# SCH_sonnn_2025-09-09_1.net
KiCad netlist of a schematic drawn in EasyEDA
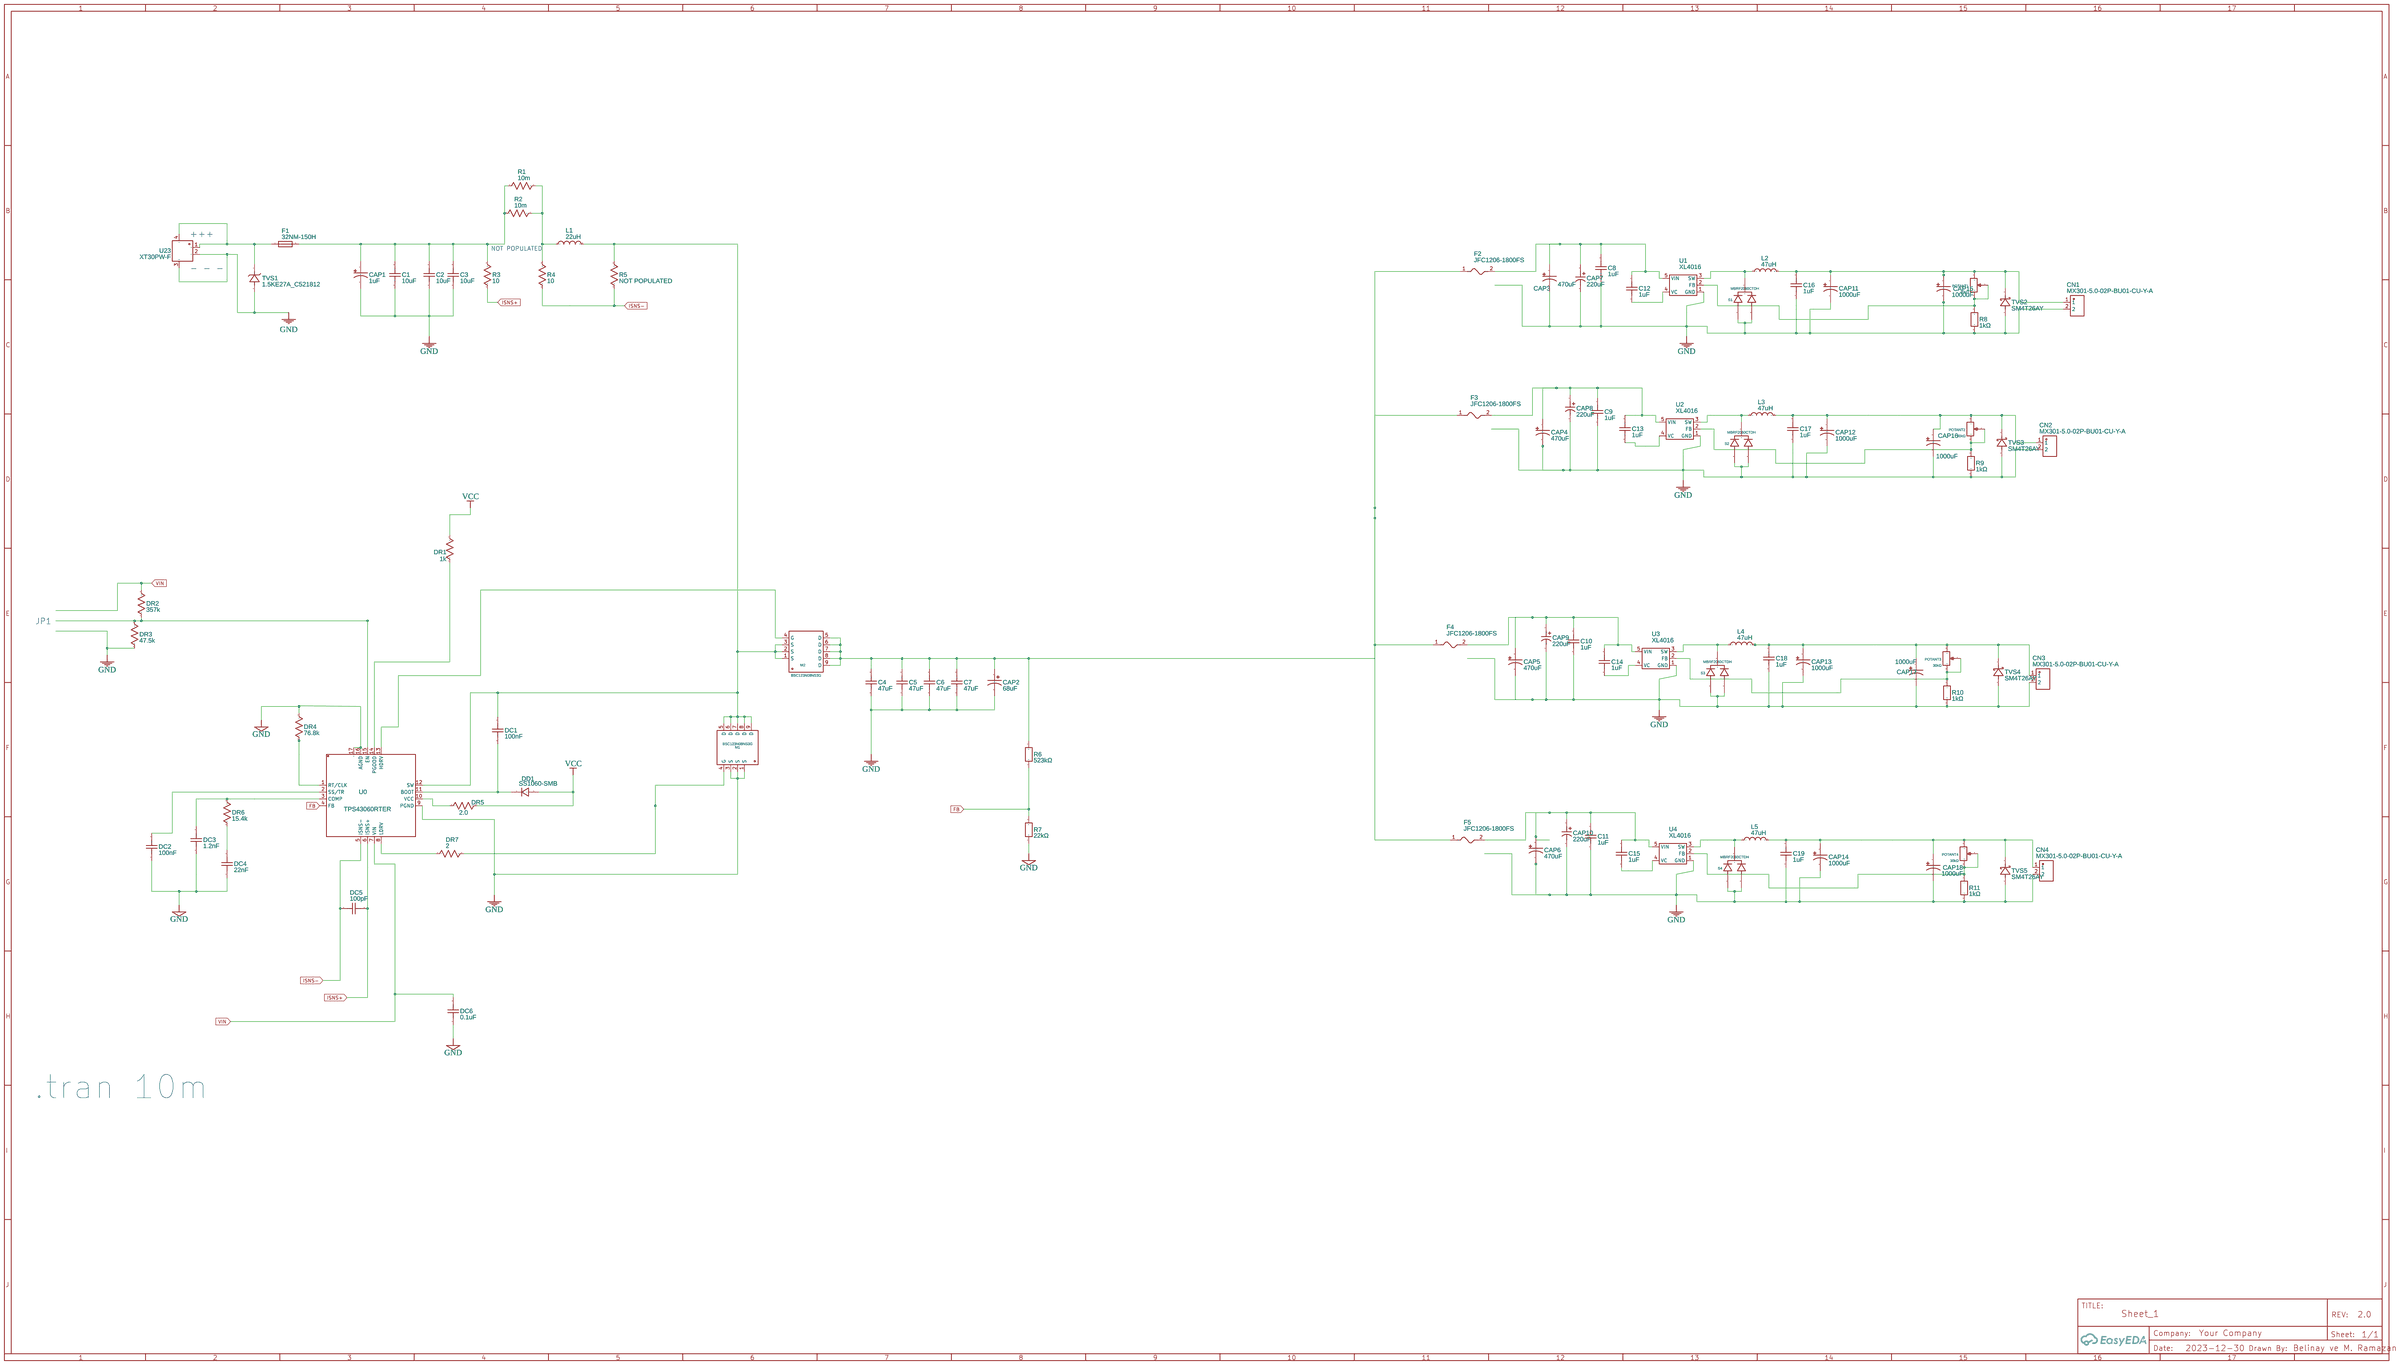
[diagram p0: schematic sheet]

(export (version "E")
  (design (tool "Eeschema 10.0.6"))
  (components
    (comp (ref "C1")
      (value "10uF")
      (fields (field (name "Manufacturer Part") "CNC6P1X7R1H106K250AE") (field (name "Manufacturer") "TDK"))
      (libsource (lib "") (part "CNC6P1X7R1H106K250AE"))
    )
    (comp (ref "C2")
      (value "10uF")
      (fields (field (name "Manufacturer Part") "CNC6P1X7R1H106K250AE") (field (name "Manufacturer") "TDK"))
      (libsource (lib "") (part "CNC6P1X7R1H106K250AE"))
    )
    (comp (ref "C3")
      (value "10uF")
      (fields (field (name "Manufacturer Part") "CNC6P1X7R1H106K250AE") (field (name "Manufacturer") "TDK"))
      (libsource (lib "") (part "CNC6P1X7R1H106K250AE"))
    )
    (comp (ref "C4") (value "47uF") (libsource (lib "") (part "C_0603_US")))
    (comp (ref "C5") (value "47uF") (libsource (lib "") (part "C_0603_US")))
    (comp (ref "C6") (value "47uF") (libsource (lib "") (part "C_0603_US")))
    (comp (ref "C7") (value "47uF") (libsource (lib "") (part "C_0603_US")))
    (comp (ref "C8")
      (value "1uF")
      (fields (field (name "Manufacturer Part") "FK26X7R1H105KRE06") (field (name "Manufacturer") "TDK"))
      (libsource (lib "") (part "FK26X7R1H105KRE06"))
    )
    (comp (ref "C9")
      (value "1uF")
      (fields (field (name "Manufacturer Part") "FK26X7R1H105KRE06") (field (name "Manufacturer") "TDK"))
      (libsource (lib "") (part "FK26X7R1H105KRE06"))
    )
    (comp (ref "C10")
      (value "1uF")
      (fields (field (name "Manufacturer Part") "FK26X7R1H105KRE06") (field (name "Manufacturer") "TDK"))
      (libsource (lib "") (part "FK26X7R1H105KRE06"))
    )
    (comp (ref "C11")
      (value "1uF")
      (fields (field (name "Manufacturer Part") "FK26X7R1H105KRE06") (field (name "Manufacturer") "TDK"))
      (libsource (lib "") (part "FK26X7R1H105KRE06"))
    )
    (comp (ref "C12")
      (value "1uF")
      (fields (field (name "Manufacturer Part") "C1005X6S1A105K050BC") (field (name "Manufacturer") "TDK"))
      (libsource (lib "") (part "C1005X6S1A105K050BC"))
    )
    (comp (ref "C13")
      (value "1uF")
      (fields (field (name "Manufacturer Part") "C1005X6S1A105K050BC") (field (name "Manufacturer") "TDK"))
      (libsource (lib "") (part "C1005X6S1A105K050BC"))
    )
    (comp (ref "C14")
      (value "1uF")
      (fields (field (name "Manufacturer Part") "C1005X6S1A105K050BC") (field (name "Manufacturer") "TDK"))
      (libsource (lib "") (part "C1005X6S1A105K050BC"))
    )
    (comp (ref "C15")
      (value "1uF")
      (fields (field (name "Manufacturer Part") "C1005X6S1A105K050BC") (field (name "Manufacturer") "TDK"))
      (libsource (lib "") (part "C1005X6S1A105K050BC_1"))
    )
    (comp (ref "C16")
      (value "1uF")
      (fields (field (name "Manufacturer Part") "FK26X7R1H105KRE06") (field (name "Manufacturer") "TDK"))
      (libsource (lib "") (part "FK26X7R1H105KRE06"))
    )
    (comp (ref "C17")
      (value "1uF")
      (fields (field (name "Manufacturer Part") "FK26X7R1H105KRE06") (field (name "Manufacturer") "TDK"))
      (libsource (lib "") (part "FK26X7R1H105KRE06_1"))
    )
    (comp (ref "C18")
      (value "1uF")
      (fields (field (name "Manufacturer Part") "FK26X7R1H105KRE06") (field (name "Manufacturer") "TDK"))
      (libsource (lib "") (part "FK26X7R1H105KRE06"))
    )
    (comp (ref "C19")
      (value "1uF")
      (fields (field (name "Manufacturer Part") "FK26X7R1H105KRE06") (field (name "Manufacturer") "TDK"))
      (libsource (lib "") (part "FK26X7R1H105KRE06"))
    )
    (comp (ref "CAP1")
      (value "1uF")
      (fields (field (name "Manufacturer Part") "HT2A1R0M0405") (field (name "Manufacturer") "HONOR(荣誉)"))
      (libsource (lib "") (part "RVT2A1R0M0405"))
    )
    (comp (ref "CAP2") (value "68uF") (libsource (lib "") (part "C_Tan_SMD_A_US")))
    (comp (ref "CAP3")
      (value "470uF")
      (fields
        (field (name "Manufacturer Part") "RC063M471LO13*20TH-2A1E")
        (field (name "Manufacturer") "BERYL(绿宝石)")
      )
      (libsource (lib "") (part "RC063M471LO13*20TH-2A1E"))
    )
    (comp (ref "CAP4")
      (value "470uF")
      (fields
        (field (name "Manufacturer Part") "RC063M471LO13*20TH-2A1E")
        (field (name "Manufacturer") "BERYL(绿宝石)")
      )
      (libsource (lib "") (part "RC063M471LO13*20TH-2A1E"))
    )
    (comp (ref "CAP5")
      (value "470uF")
      (fields
        (field (name "Manufacturer Part") "RC063M471LO13*20TH-2A1E")
        (field (name "Manufacturer") "BERYL(绿宝石)")
      )
      (libsource (lib "") (part "RC063M471LO13*20TH-2A1E"))
    )
    (comp (ref "CAP6")
      (value "470uF")
      (fields
        (field (name "Manufacturer Part") "RC063M471LO13*20TH-2A1E")
        (field (name "Manufacturer") "BERYL(绿宝石)")
      )
      (libsource (lib "") (part "RC063M471LO13*20TH-2A1E_1"))
    )
    (comp (ref "CAP7")
      (value "220uF")
      (fields (field (name "Manufacturer Part") "189RV0038") (field (name "Manufacturer") "KNSCHA(科尼盛)"))
      (libsource (lib "") (part "189RV0038"))
    )
    (comp (ref "CAP8")
      (value "220uF")
      (fields (field (name "Manufacturer Part") "189RV0038") (field (name "Manufacturer") "KNSCHA(科尼盛)"))
      (libsource (lib "") (part "189RV0038"))
    )
    (comp (ref "CAP9")
      (value "220uF")
      (fields (field (name "Manufacturer Part") "189RV0038") (field (name "Manufacturer") "KNSCHA(科尼盛)"))
      (libsource (lib "") (part "189RV0038"))
    )
    (comp (ref "CAP10")
      (value "220uF")
      (fields (field (name "Manufacturer Part") "189RV0038") (field (name "Manufacturer") "KNSCHA(科尼盛)"))
      (libsource (lib "") (part "189RV0038"))
    )
    (comp (ref "CAP11")
      (value "1000uF")
      (fields (field (name "Manufacturer Part") "PKCL2001H102MF") (field (name "Manufacturer") "Ymin(永铭)"))
      (libsource (lib "") (part "PKCL21H102MF"))
    )
    (comp (ref "CAP12")
      (value "1000uF")
      (fields (field (name "Manufacturer Part") "PKCL2001H102MF") (field (name "Manufacturer") "Ymin(永铭)"))
      (libsource (lib "") (part "PKCL21H102MF"))
    )
    (comp (ref "CAP13")
      (value "1000uF")
      (fields (field (name "Manufacturer Part") "PKCL2001H102MF") (field (name "Manufacturer") "Ymin(永铭)"))
      (libsource (lib "") (part "PKCL21H102MF"))
    )
    (comp (ref "CAP14")
      (value "1000uF")
      (fields (field (name "Manufacturer Part") "PKCL2001H102MF") (field (name "Manufacturer") "Ymin(永铭)"))
      (libsource (lib "") (part "PKCL21H102MF_1"))
    )
    (comp (ref "CAP15")
      (value "1000uF")
      (fields (field (name "Manufacturer Part") "LKML3001J102MF") (field (name "Manufacturer") "Ymin(永铭)"))
      (libsource (lib "") (part "LKML3001J102MF"))
    )
    (comp (ref "CAP16")
      (value "1000uF")
      (fields (field (name "Manufacturer Part") "LKML3001J102MF") (field (name "Manufacturer") "Ymin(永铭)"))
      (libsource (lib "") (part "LKML3001J102MF"))
    )
    (comp (ref "CAP17")
      (value "1000uF")
      (fields (field (name "Manufacturer Part") "LKML3001J102MF") (field (name "Manufacturer") "Ymin(永铭)"))
      (libsource (lib "") (part "LKML3001J102MF_1"))
    )
    (comp (ref "CAP18")
      (value "1000uF")
      (fields (field (name "Manufacturer Part") "LKML3001J102MF") (field (name "Manufacturer") "Ymin(永铭)"))
      (libsource (lib "") (part "LKML3001J102MF_1"))
    )
    (comp (ref "CN1")
      (value "MX301-5.0-02P-BU01-CU-Y-A")
      (fields
        (field (name "Manufacturer Part") "MX301-5.0-02P-BU01-Cu-Y-A")
        (field (name "Manufacturer") "MAX(迈旭)")
      )
      (libsource (lib "") (part "MX301-5.0-02P-BU01-CU-Y-A"))
    )
    (comp (ref "CN2")
      (value "MX301-5.0-02P-BU01-CU-Y-A")
      (fields
        (field (name "Manufacturer Part") "MX301-5.0-02P-BU01-Cu-Y-A")
        (field (name "Manufacturer") "MAX(迈旭)")
      )
      (libsource (lib "") (part "MX301-5.0-02P-BU01-CU-Y-A"))
    )
    (comp (ref "CN3")
      (value "MX301-5.0-02P-BU01-CU-Y-A")
      (fields
        (field (name "Manufacturer Part") "MX301-5.0-02P-BU01-Cu-Y-A")
        (field (name "Manufacturer") "MAX(迈旭)")
      )
      (libsource (lib "") (part "MX301-5.0-02P-BU01-CU-Y-A"))
    )
    (comp (ref "CN4")
      (value "MX301-5.0-02P-BU01-CU-Y-A")
      (fields
        (field (name "Manufacturer Part") "MX301-5.0-02P-BU01-Cu-Y-A")
        (field (name "Manufacturer") "MAX(迈旭)")
      )
      (libsource (lib "") (part "MX301-5.0-02P-BU01-CU-Y-A"))
    )
    (comp (ref "DC1")
      (value "100nF")
      (fields
        (field (name "Manufacturer Part") "DCS104M26Y5UH6FJ5A0")
        (field (name "Manufacturer") "SHM(南方宏明)")
      )
      (libsource (lib "") (part "DCS104M26Y5UH6FJ5A0"))
    )
    (comp (ref "DC2")
      (value "100nF")
      (fields
        (field (name "Manufacturer Part") "DCS104M26Y5UH6FJ5A0")
        (field (name "Manufacturer") "SHM(南方宏明)")
      )
      (libsource (lib "") (part "DCS104M26Y5UH6FJ5A0_1"))
    )
    (comp (ref "DC3")
      (value "1.2nF")
      (fields (field (name "Manufacturer Part") "PE122J2A0501") (field (name "Manufacturer") "KYET(科雅)"))
      (libsource (lib "") (part "PE122J2A0501"))
    )
    (comp (ref "DC4")
      (value "22nF")
      (fields
        (field (name "Manufacturer Part") "DCM223M39Y5VL6FJ5A0")
        (field (name "Manufacturer") "SHM(南方宏明)")
      )
      (libsource (lib "") (part "DCM223M39Y5VL6FJ5A0"))
    )
    (comp (ref "DC5")
      (value "100pF")
      (fields
        (field (name "Manufacturer Part") "DCC101J26COHF6FJ5A0")
        (field (name "Manufacturer") "SHM(南方宏明)")
      )
      (libsource (lib "") (part "DCC101J26COHF6FJ5A0"))
    )
    (comp (ref "DC6") (value "0.1uF") (libsource (lib "") (part "C_0603_US_1")))
    (comp (ref "DD1")
      (value "SS1060-SMB")
      (fields (field (name "Manufacturer") "GOODWORK(固得沃克)"))
      (libsource (lib "") (part "SS1060-SMB"))
    )
    (comp (ref "DR1") (value "1k") (libsource (lib "") (part "R_AXIAL-0.3_US")))
    (comp (ref "DR2") (value "357k") (libsource (lib "") (part "R_AXIAL-0.3_US")))
    (comp (ref "DR3") (value "47.5k") (libsource (lib "") (part "R_AXIAL-0.3_US")))
    (comp (ref "DR4") (value "76.8k") (libsource (lib "") (part "R_AXIAL-0.3_US")))
    (comp (ref "DR5") (value "2.0") (libsource (lib "") (part "R_AXIAL-0.3_US_3")))
    (comp (ref "DR6") (value "15.4k") (libsource (lib "") (part "R_AXIAL-0.3_US")))
    (comp (ref "DR7") (value "2") (libsource (lib "") (part "R_0603_US")))
    (comp (ref "F1")
      (value "32NM-150H")
      (fields (field (name "Manufacturer") "HOLLY(好利来)"))
      (libsource (lib "") (part "32NM-150H"))
    )
    (comp (ref "F2")
      (value "JFC1206-1800FS")
      (fields (field (name "Manufacturer") "JDTfuse(集电通)"))
      (libsource (lib "") (part "JFC1206-1800FS"))
    )
    (comp (ref "F3")
      (value "JFC1206-1800FS")
      (fields (field (name "Manufacturer") "JDTfuse(集电通)"))
      (libsource (lib "") (part "JFC1206-1800FS"))
    )
    (comp (ref "F4")
      (value "JFC1206-1800FS")
      (fields (field (name "Manufacturer") "JDTfuse(集电通)"))
      (libsource (lib "") (part "JFC1206-1800FS"))
    )
    (comp (ref "F5")
      (value "JFC1206-1800FS")
      (fields (field (name "Manufacturer") "JDTfuse(集电通)"))
      (libsource (lib "") (part "JFC1206-1800FS"))
    )
    (comp (ref "L1")
      (value "22uH")
      (fields
        (field (name "Manufacturer Part") "PDMTAT068125-220MLU")
        (field (name "Manufacturer") "PROD(谱罗德)")
      )
      (libsource (lib "") (part "PDMTAT068125-220MLU"))
    )
    (comp (ref "L2")
      (value "47uH")
      (fields (field (name "Manufacturer Part") "PDPMAA1712-470MP") (field (name "Manufacturer") "PROD(谱罗德)"))
      (libsource (lib "") (part "PDPMAA1712-470MP"))
    )
    (comp (ref "L3")
      (value "47uH")
      (fields (field (name "Manufacturer Part") "PDPMAA1712-470MP") (field (name "Manufacturer") "PROD(谱罗德)"))
      (libsource (lib "") (part "PDPMAA1712-470MP"))
    )
    (comp (ref "L4")
      (value "47uH")
      (fields (field (name "Manufacturer Part") "PDPMAA1712-470MP") (field (name "Manufacturer") "PROD(谱罗德)"))
      (libsource (lib "") (part "PDPMAA1712-470MP"))
    )
    (comp (ref "L5")
      (value "47uH")
      (fields (field (name "Manufacturer Part") "PDPMAA1712-470MP") (field (name "Manufacturer") "PROD(谱罗德)"))
      (libsource (lib "") (part "PDPMAA1712-470MP"))
    )
    (comp (ref "M1")
      (value "BSC123N08NS3G")
      (fields (field (name "Manufacturer") "Infineon(英飞凌)"))
      (libsource (lib "") (part "BSC123N08NS3G"))
    )
    (comp (ref "M2")
      (value "BSC123N08NS3G")
      (fields (field (name "Manufacturer") "Infineon(英飞凌)"))
      (libsource (lib "") (part "BSC123N08NS3G_1"))
    )
    (comp (ref "POTANT1")
      (value "30kΩ")
      (fields (field (name "Manufacturer Part") "3362P-1-103LF") (field (name "Manufacturer") "BOURNS"))
      (libsource (lib "") (part "3362P-1-103LF"))
    )
    (comp (ref "POTANT2")
      (value "30kΩ")
      (fields (field (name "Manufacturer Part") "3362P-1-103LF") (field (name "Manufacturer") "BOURNS"))
      (libsource (lib "") (part "3362P-1-103LF"))
    )
    (comp (ref "POTANT3")
      (value "30kΩ")
      (fields (field (name "Manufacturer Part") "3362P-1-103LF") (field (name "Manufacturer") "BOURNS"))
      (libsource (lib "") (part "3362P-1-103LF"))
    )
    (comp (ref "POTANT4")
      (value "30kΩ")
      (fields (field (name "Manufacturer Part") "3362P-1-103LF") (field (name "Manufacturer") "BOURNS"))
      (libsource (lib "") (part "3362P-1-103LF"))
    )
    (comp (ref "R1") (value "10m") (libsource (lib "") (part "R_AXIAL-0.3_US_2")))
    (comp (ref "R2") (value "10m") (libsource (lib "") (part "R_AXIAL-0.3_US_2")))
    (comp (ref "R3") (value "10") (libsource (lib "") (part "R_AXIAL-0.3_US_1")))
    (comp (ref "R4") (value "10") (libsource (lib "") (part "R_AXIAL-0.3_US_1")))
    (comp (ref "R5") (value "NOT POPULATED") (libsource (lib "") (part "R_AXIAL-0.3_US_1")))
    (comp (ref "R6")
      (value "523kΩ")
      (fields (field (name "Manufacturer Part") "MFR-25FBF52-523K") (field (name "Manufacturer") "YAGEO(国巨)"))
      (libsource (lib "") (part "MFR-25FBF52-523K"))
    )
    (comp (ref "R7")
      (value "22kΩ")
      (fields
        (field (name "Manufacturer Part") "RN 3WS 22K F T/B A1")
        (field (name "Manufacturer") "Tyohm(幸亚电阻)")
      )
      (libsource (lib "") (part "RN 3WS 22K F T/B A1"))
    )
    (comp (ref "R8")
      (value "1kΩ")
      (fields (field (name "Manufacturer Part") "MF0207FTE52-1K") (field (name "Manufacturer") "YAGEO(国巨)"))
      (libsource (lib "") (part "MF0207FTE52-1K"))
    )
    (comp (ref "R9")
      (value "1kΩ")
      (fields (field (name "Manufacturer Part") "MF0207FTE52-1K") (field (name "Manufacturer") "YAGEO(国巨)"))
      (libsource (lib "") (part "MF0207FTE52-1K"))
    )
    (comp (ref "R10")
      (value "1kΩ")
      (fields (field (name "Manufacturer Part") "MF0207FTE52-1K") (field (name "Manufacturer") "YAGEO(国巨)"))
      (libsource (lib "") (part "MF0207FTE52-1K"))
    )
    (comp (ref "R11")
      (value "1kΩ")
      (fields (field (name "Manufacturer Part") "MF0207FTE52-1K") (field (name "Manufacturer") "YAGEO(国巨)"))
      (libsource (lib "") (part "MF0207FTE52-1K"))
    )
    (comp (ref "S1")
      (value "MBRF2060CTDH")
      (fields (field (name "Manufacturer") "迪一"))
      (libsource (lib "") (part "MBRF2060CTDH"))
    )
    (comp (ref "S2")
      (value "MBRF2060CTDH")
      (fields (field (name "Manufacturer") "迪一"))
      (libsource (lib "") (part "MBRF2060CTDH"))
    )
    (comp (ref "S3")
      (value "MBRF2060CTDH")
      (fields (field (name "Manufacturer") "迪一"))
      (libsource (lib "") (part "MBRF2060CTDH"))
    )
    (comp (ref "S4")
      (value "MBRF2060CTDH")
      (fields (field (name "Manufacturer") "迪一"))
      (libsource (lib "") (part "MBRF2060CTDH"))
    )
    (comp (ref "TVS1")
      (value "1.5KE27A_C521812")
      (fields
        (field (name "Manufacturer Part") "1.5KE27A/B")
        (field (name "Manufacturer") "Brightking(君耀电子)")
      )
      (libsource (lib "") (part "1.5KE27A_C521812"))
    )
    (comp (ref "TVS2")
      (value "SM4T26AY")
      (fields (field (name "Manufacturer") "ST(意法半导体)"))
      (libsource (lib "") (part "SM4T26AY"))
    )
    (comp (ref "TVS3")
      (value "SM4T26AY")
      (fields (field (name "Manufacturer") "ST(意法半导体)"))
      (libsource (lib "") (part "SM4T26AY"))
    )
    (comp (ref "TVS4")
      (value "SM4T26AY")
      (fields (field (name "Manufacturer") "ST(意法半导体)"))
      (libsource (lib "") (part "SM4T26AY"))
    )
    (comp (ref "TVS5")
      (value "SM4T26AY")
      (fields (field (name "Manufacturer") "ST(意法半导体)"))
      (libsource (lib "") (part "SM4T26AY"))
    )
    (comp (ref "U0")
      (value "TPS43060RTER")
      (fields (field (name "Manufacturer") "TI(德州仪器)"))
      (libsource (lib "") (part "TPS43060RTER"))
    )
    (comp (ref "U1")
      (value "XL4016")
      (fields (field (name "Manufacturer Part") "XL4016E1") (field (name "Manufacturer") "XLSEMI"))
      (libsource (lib "") (part "XL4016"))
    )
    (comp (ref "U2")
      (value "XL4016")
      (fields (field (name "Manufacturer Part") "XL4016E1") (field (name "Manufacturer") "XLSEMI"))
      (libsource (lib "") (part "XL4016"))
    )
    (comp (ref "U3")
      (value "XL4016")
      (fields (field (name "Manufacturer Part") "XL4016E1") (field (name "Manufacturer") "XLSEMI"))
      (libsource (lib "") (part "XL4016"))
    )
    (comp (ref "U4")
      (value "XL4016")
      (fields (field (name "Manufacturer Part") "XL4016E1") (field (name "Manufacturer") "XLSEMI"))
      (libsource (lib "") (part "XL4016"))
    )
    (comp (ref "U23") (value "XT30PW-F") (libsource (lib "") (part "XT30PW-F")))
  )
  (nets
    (net (code "1") (name "FB") (class "Default")
      (node (ref "R6") (pin "1") (pinfunction "1_1") (pintype "unspecified"))
      (node (ref "R7") (pin "1") (pinfunction "1_1") (pintype "unspecified"))
      (node (ref "U0") (pin "4") (pinfunction "FB_4") (pintype "unspecified"))
    )
    (net (code "2") (name "GND") (class "Default")
      (node (ref "C1") (pin "1") (pinfunction "1_1") (pintype "unspecified"))
      (node (ref "C10") (pin "2") (pinfunction "2_2") (pintype "unspecified"))
      (node (ref "C11") (pin "2") (pinfunction "2_2") (pintype "unspecified"))
      (node (ref "C16") (pin "2") (pinfunction "2_2") (pintype "unspecified"))
      (node (ref "C17") (pin "1") (pinfunction "1_1") (pintype "unspecified"))
      (node (ref "C18") (pin "2") (pinfunction "2_2") (pintype "unspecified"))
      (node (ref "C19") (pin "2") (pinfunction "2_2") (pintype "unspecified"))
      (node (ref "C2") (pin "1") (pinfunction "1_1") (pintype "unspecified"))
      (node (ref "C3") (pin "1") (pinfunction "1_1") (pintype "unspecified"))
      (node (ref "C4") (pin "1") (pinfunction "1_1") (pintype "unspecified"))
      (node (ref "C5") (pin "1") (pinfunction "1_1") (pintype "unspecified"))
      (node (ref "C6") (pin "1") (pinfunction "1_1") (pintype "unspecified"))
      (node (ref "C7") (pin "1") (pinfunction "1_1") (pintype "unspecified"))
      (node (ref "C8") (pin "2") (pinfunction "2_2") (pintype "unspecified"))
      (node (ref "C9") (pin "2") (pinfunction "2_2") (pintype "unspecified"))
      (node (ref "CAP1") (pin "2") (pinfunction "2_2") (pintype "unspecified"))
      (node (ref "CAP10") (pin "2") (pinfunction "2_2") (pintype "input"))
      (node (ref "CAP11") (pin "2") (pinfunction "2_2") (pintype "unspecified"))
      (node (ref "CAP12") (pin "2") (pinfunction "2_2") (pintype "unspecified"))
      (node (ref "CAP13") (pin "2") (pinfunction "2_2") (pintype "unspecified"))
      (node (ref "CAP14") (pin "2") (pinfunction "2_2") (pintype "unspecified"))
      (node (ref "CAP15") (pin "2") (pinfunction "2_2") (pintype "unspecified"))
      (node (ref "CAP16") (pin "2") (pinfunction "2_2") (pintype "unspecified"))
      (node (ref "CAP17") (pin "2") (pinfunction "2_2") (pintype "unspecified"))
      (node (ref "CAP18") (pin "2") (pinfunction "2_2") (pintype "unspecified"))
      (node (ref "CAP2") (pin "2") (pinfunction "2_2") (pintype "unspecified"))
      (node (ref "CAP3") (pin "2") (pinfunction "2_2") (pintype "unspecified"))
      (node (ref "CAP4") (pin "2") (pinfunction "2_2") (pintype "unspecified"))
      (node (ref "CAP5") (pin "2") (pinfunction "2_2") (pintype "unspecified"))
      (node (ref "CAP6") (pin "2") (pinfunction "2_2") (pintype "unspecified"))
      (node (ref "CAP7") (pin "2") (pinfunction "2_2") (pintype "input"))
      (node (ref "CAP8") (pin "2") (pinfunction "2_2") (pintype "input"))
      (node (ref "CAP9") (pin "2") (pinfunction "2_2") (pintype "input"))
      (node (ref "CN1") (pin "2") (pinfunction "2_2") (pintype "unspecified"))
      (node (ref "CN2") (pin "2") (pinfunction "2_2") (pintype "unspecified"))
      (node (ref "CN3") (pin "2") (pinfunction "2_2") (pintype "unspecified"))
      (node (ref "CN4") (pin "2") (pinfunction "2_2") (pintype "unspecified"))
      (node (ref "DC2") (pin "1") (pinfunction "1_1") (pintype "unspecified"))
      (node (ref "DC3") (pin "1") (pinfunction "1_1") (pintype "unspecified"))
      (node (ref "DC4") (pin "1") (pinfunction "1_1") (pintype "unspecified"))
      (node (ref "DC6") (pin "1") (pinfunction "1_1") (pintype "unspecified"))
      (node (ref "DR3") (pin "1") (pinfunction "1_1") (pintype "unspecified"))
      (node (ref "DR4") (pin "2") (pinfunction "2_2") (pintype "unspecified"))
      (node (ref "M1") (pin "1") (pinfunction "S_1") (pintype "unspecified"))
      (node (ref "M1") (pin "2") (pinfunction "S_2") (pintype "unspecified"))
      (node (ref "M1") (pin "3") (pinfunction "S_3") (pintype "unspecified"))
      (node (ref "R10") (pin "2") (pinfunction "2_2") (pintype "unspecified"))
      (node (ref "R11") (pin "2") (pinfunction "2_2") (pintype "unspecified"))
      (node (ref "R7") (pin "2") (pinfunction "2_2") (pintype "unspecified"))
      (node (ref "R8") (pin "2") (pinfunction "2_2") (pintype "unspecified"))
      (node (ref "R9") (pin "2") (pinfunction "2_2") (pintype "unspecified"))
      (node (ref "S1") (pin "1") (pinfunction "1_1") (pintype "unspecified"))
      (node (ref "S1") (pin "3") (pinfunction "3_3") (pintype "unspecified"))
      (node (ref "S2") (pin "1") (pinfunction "1_1") (pintype "unspecified"))
      (node (ref "S2") (pin "3") (pinfunction "3_3") (pintype "unspecified"))
      (node (ref "S3") (pin "1") (pinfunction "1_1") (pintype "unspecified"))
      (node (ref "S3") (pin "3") (pinfunction "3_3") (pintype "unspecified"))
      (node (ref "S4") (pin "1") (pinfunction "1_1") (pintype "unspecified"))
      (node (ref "S4") (pin "3") (pinfunction "3_3") (pintype "unspecified"))
      (node (ref "TVS1") (pin "2") (pinfunction "A_2") (pintype "unspecified"))
      (node (ref "TVS2") (pin "2") (pinfunction "2_2") (pintype "unspecified"))
      (node (ref "TVS3") (pin "2") (pinfunction "2_2") (pintype "unspecified"))
      (node (ref "TVS4") (pin "2") (pinfunction "2_2") (pintype "unspecified"))
      (node (ref "TVS5") (pin "2") (pinfunction "2_2") (pintype "unspecified"))
      (node (ref "U0") (pin "16") (pinfunction "AGND_16") (pintype "unspecified"))
      (node (ref "U0") (pin "17") (pinfunction "PAD_17") (pintype "unspecified"))
      (node (ref "U0") (pin "9") (pinfunction "PGND_9") (pintype "unspecified"))
      (node (ref "U1") (pin "1") (pinfunction "GND_1") (pintype "unspecified"))
      (node (ref "U2") (pin "1") (pinfunction "GND_1") (pintype "unspecified"))
      (node (ref "U23") (pin "2") (pinfunction "2_2") (pintype "unspecified"))
      (node (ref "U23") (pin "3") (pinfunction "3_3") (pintype "unspecified"))
      (node (ref "U3") (pin "1") (pinfunction "GND_1") (pintype "unspecified"))
      (node (ref "U4") (pin "1") (pinfunction "GND_1") (pintype "unspecified"))
    )
    (net (code "3") (name "ISNS+") (class "Default")
      (node (ref "DC5") (pin "2") (pinfunction "2_2") (pintype "unspecified"))
      (node (ref "R3") (pin "1") (pinfunction "1_1") (pintype "unspecified"))
      (node (ref "U0") (pin "6") (pinfunction "ISNS+_6") (pintype "unspecified"))
    )
    (net (code "4") (name "ISNS-") (class "Default")
      (node (ref "DC5") (pin "1") (pinfunction "1_1") (pintype "unspecified"))
      (node (ref "R4") (pin "1") (pinfunction "1_1") (pintype "unspecified"))
      (node (ref "R5") (pin "1") (pinfunction "1_1") (pintype "unspecified"))
      (node (ref "U0") (pin "5") (pinfunction "ISNS-_5") (pintype "unspecified"))
    )
    (net (code "5") (name "Net-(C1-Pad2)") (class "Default")
      (node (ref "C1") (pin "2") (pinfunction "2_2") (pintype "unspecified"))
      (node (ref "C2") (pin "2") (pinfunction "2_2") (pintype "unspecified"))
      (node (ref "C3") (pin "2") (pinfunction "2_2") (pintype "unspecified"))
      (node (ref "CAP1") (pin "1") (pinfunction "1_1") (pintype "unspecified"))
      (node (ref "F1") (pin "2") (pinfunction "2_2") (pintype "unspecified"))
      (node (ref "R1") (pin "1") (pinfunction "1_1") (pintype "unspecified"))
      (node (ref "R2") (pin "1") (pinfunction "1_1") (pintype "unspecified"))
      (node (ref "R3") (pin "2") (pinfunction "2_2") (pintype "unspecified"))
    )
    (net (code "6") (name "Net-(C4-Pad2)") (class "Default")
      (node (ref "C4") (pin "2") (pinfunction "2_2") (pintype "unspecified"))
      (node (ref "C5") (pin "2") (pinfunction "2_2") (pintype "unspecified"))
      (node (ref "C6") (pin "2") (pinfunction "2_2") (pintype "unspecified"))
      (node (ref "C7") (pin "2") (pinfunction "2_2") (pintype "unspecified"))
      (node (ref "CAP2") (pin "1") (pinfunction "1_1") (pintype "unspecified"))
      (node (ref "F2") (pin "1") (pinfunction "1_1") (pintype "unspecified"))
      (node (ref "F3") (pin "1") (pinfunction "1_1") (pintype "unspecified"))
      (node (ref "F4") (pin "1") (pinfunction "1_1") (pintype "unspecified"))
      (node (ref "F5") (pin "1") (pinfunction "1_1") (pintype "unspecified"))
      (node (ref "M2") (pin "5") (pinfunction "D_5") (pintype "unspecified"))
      (node (ref "M2") (pin "6") (pinfunction "D_6") (pintype "unspecified"))
      (node (ref "M2") (pin "7") (pinfunction "D_7") (pintype "unspecified"))
      (node (ref "M2") (pin "8") (pinfunction "D_8") (pintype "unspecified"))
      (node (ref "M2") (pin "9") (pinfunction "D_9") (pintype "unspecified"))
      (node (ref "R6") (pin "2") (pinfunction "2_2") (pintype "unspecified"))
    )
    (net (code "7") (name "Net-(C16-Pad1)") (class "Default")
      (node (ref "C16") (pin "1") (pinfunction "1_1") (pintype "unspecified"))
      (node (ref "CAP11") (pin "1") (pinfunction "1_1") (pintype "unspecified"))
      (node (ref "CAP15") (pin "1") (pinfunction "1_1") (pintype "unspecified"))
      (node (ref "CN1") (pin "1") (pinfunction "1_1") (pintype "unspecified"))
      (node (ref "L2") (pin "2") (pinfunction "2_2") (pintype "unspecified"))
      (node (ref "POTANT1") (pin "1") (pinfunction "1_1") (pintype "input"))
      (node (ref "TVS2") (pin "1") (pinfunction "1_1") (pintype "unspecified"))
    )
    (net (code "8") (name "Net-(C17-Pad2)") (class "Default")
      (node (ref "C17") (pin "2") (pinfunction "2_2") (pintype "unspecified"))
      (node (ref "CAP12") (pin "1") (pinfunction "1_1") (pintype "unspecified"))
      (node (ref "CAP16") (pin "1") (pinfunction "1_1") (pintype "unspecified"))
      (node (ref "CN2") (pin "1") (pinfunction "1_1") (pintype "unspecified"))
      (node (ref "L3") (pin "2") (pinfunction "2_2") (pintype "unspecified"))
      (node (ref "POTANT2") (pin "1") (pinfunction "1_1") (pintype "input"))
      (node (ref "TVS3") (pin "1") (pinfunction "1_1") (pintype "unspecified"))
    )
    (net (code "9") (name "Net-(C18-Pad1)") (class "Default")
      (node (ref "C18") (pin "1") (pinfunction "1_1") (pintype "unspecified"))
      (node (ref "CAP13") (pin "1") (pinfunction "1_1") (pintype "unspecified"))
      (node (ref "CAP17") (pin "1") (pinfunction "1_1") (pintype "unspecified"))
      (node (ref "CN3") (pin "1") (pinfunction "1_1") (pintype "unspecified"))
      (node (ref "L4") (pin "2") (pinfunction "2_2") (pintype "unspecified"))
      (node (ref "POTANT3") (pin "1") (pinfunction "1_1") (pintype "input"))
      (node (ref "TVS4") (pin "1") (pinfunction "1_1") (pintype "unspecified"))
    )
    (net (code "10") (name "Net-(C19-Pad1)") (class "Default")
      (node (ref "C19") (pin "1") (pinfunction "1_1") (pintype "unspecified"))
      (node (ref "CAP14") (pin "1") (pinfunction "1_1") (pintype "unspecified"))
      (node (ref "CAP18") (pin "1") (pinfunction "1_1") (pintype "unspecified"))
      (node (ref "CN4") (pin "1") (pinfunction "1_1") (pintype "unspecified"))
      (node (ref "L5") (pin "2") (pinfunction "2_2") (pintype "unspecified"))
      (node (ref "POTANT4") (pin "1") (pinfunction "1_1") (pintype "input"))
      (node (ref "TVS5") (pin "1") (pinfunction "1_1") (pintype "unspecified"))
    )
    (net (code "11") (name "Net-(DC4-Pad2)") (class "Default")
      (node (ref "DC4") (pin "2") (pinfunction "2_2") (pintype "unspecified"))
      (node (ref "DR6") (pin "1") (pinfunction "1_1") (pintype "unspecified"))
    )
    (net (code "12") (name "Net-(DD1-C)") (class "Default")
      (node (ref "DC1") (pin "2") (pinfunction "2_2") (pintype "unspecified"))
      (node (ref "DD1") (pin "1") (pinfunction "C_1") (pintype "unspecified"))
      (node (ref "U0") (pin "11") (pinfunction "BOOT_11") (pintype "unspecified"))
    )
    (net (code "13") (name "Net-(L1-Pad1)") (class "Default")
      (node (ref "L1") (pin "1") (pinfunction "1_1") (pintype "unspecified"))
      (node (ref "R1") (pin "2") (pinfunction "2_2") (pintype "unspecified"))
      (node (ref "R2") (pin "2") (pinfunction "2_2") (pintype "unspecified"))
      (node (ref "R4") (pin "2") (pinfunction "2_2") (pintype "unspecified"))
    )
    (net (code "14") (name "Net-(M1-G)") (class "Default")
      (node (ref "DR7") (pin "2") (pinfunction "2_2") (pintype "unspecified"))
      (node (ref "M1") (pin "4") (pinfunction "G_4") (pintype "unspecified"))
    )
    (net (code "15") (name "Net-(M2-G)") (class "Default")
      (node (ref "M2") (pin "4") (pinfunction "G_4") (pintype "unspecified"))
      (node (ref "U0") (pin "13") (pinfunction "HDRV_13") (pintype "unspecified"))
    )
    (net (code "16") (name "Net-(TVS1-C)") (class "Default")
      (node (ref "F1") (pin "1") (pinfunction "1_1") (pintype "unspecified"))
      (node (ref "TVS1") (pin "1") (pinfunction "C_1") (pintype "unspecified"))
      (node (ref "U23") (pin "1") (pinfunction "1_1") (pintype "unspecified"))
      (node (ref "U23") (pin "4") (pinfunction "4_4") (pintype "unspecified"))
    )
    (net (code "17") (name "Net-(U0-COMP)") (class "Default")
      (node (ref "DC3") (pin "2") (pinfunction "2_2") (pintype "unspecified"))
      (node (ref "DR6") (pin "2") (pinfunction "2_2") (pintype "unspecified"))
      (node (ref "U0") (pin "3") (pinfunction "COMP_3") (pintype "unspecified"))
    )
    (net (code "18") (name "Net-(U0-EN)") (class "Default")
      (node (ref "DR2") (pin "1") (pinfunction "1_1") (pintype "unspecified"))
      (node (ref "DR3") (pin "2") (pinfunction "2_2") (pintype "unspecified"))
      (node (ref "U0") (pin "15") (pinfunction "EN_15") (pintype "unspecified"))
    )
    (net (code "19") (name "Net-(U0-LDRV)") (class "Default")
      (node (ref "DR7") (pin "1") (pinfunction "1_1") (pintype "unspecified"))
      (node (ref "U0") (pin "8") (pinfunction "LDRV_8") (pintype "unspecified"))
    )
    (net (code "20") (name "Net-(U0-PGOOD)") (class "Default")
      (node (ref "DR1") (pin "1") (pinfunction "1_1") (pintype "unspecified"))
      (node (ref "U0") (pin "14") (pinfunction "PGOOD_14") (pintype "unspecified"))
    )
    (net (code "21") (name "Net-(U0-RT{slash}CLK)") (class "Default")
      (node (ref "DR4") (pin "1") (pinfunction "1_1") (pintype "unspecified"))
      (node (ref "U0") (pin "1") (pinfunction "RT/CLK_1") (pintype "unspecified"))
    )
    (net (code "22") (name "Net-(U0-SS{slash}TR)") (class "Default")
      (node (ref "DC2") (pin "2") (pinfunction "2_2") (pintype "unspecified"))
      (node (ref "U0") (pin "2") (pinfunction "SS/TR_2") (pintype "unspecified"))
    )
    (net (code "23") (name "Net-(U0-SW)") (class "Default")
      (node (ref "DC1") (pin "1") (pinfunction "1_1") (pintype "unspecified"))
      (node (ref "L1") (pin "2") (pinfunction "2_2") (pintype "unspecified"))
      (node (ref "M1") (pin "5") (pinfunction "D_5") (pintype "unspecified"))
      (node (ref "M1") (pin "6") (pinfunction "D_6") (pintype "unspecified"))
      (node (ref "M1") (pin "7") (pinfunction "D_7") (pintype "unspecified"))
      (node (ref "M1") (pin "8") (pinfunction "D_8") (pintype "unspecified"))
      (node (ref "M1") (pin "9") (pinfunction "D_9") (pintype "unspecified"))
      (node (ref "M2") (pin "1") (pinfunction "S_1") (pintype "unspecified"))
      (node (ref "M2") (pin "2") (pinfunction "S_2") (pintype "unspecified"))
      (node (ref "M2") (pin "3") (pinfunction "S_3") (pintype "unspecified"))
      (node (ref "R5") (pin "2") (pinfunction "2_2") (pintype "unspecified"))
      (node (ref "U0") (pin "12") (pinfunction "SW_12") (pintype "unspecified"))
    )
    (net (code "24") (name "Net-(U0-VCC)") (class "Default")
      (node (ref "DR5") (pin "1") (pinfunction "1_1") (pintype "unspecified"))
      (node (ref "U0") (pin "10") (pinfunction "VCC_10") (pintype "unspecified"))
    )
    (net (code "25") (name "Net-(U1-FB)") (class "Default")
      (node (ref "POTANT1") (pin "2") (pinfunction "2_2") (pintype "input"))
      (node (ref "POTANT1") (pin "3") (pinfunction "3_3") (pintype "input"))
      (node (ref "R8") (pin "1") (pinfunction "1_1") (pintype "unspecified"))
      (node (ref "U1") (pin "2") (pinfunction "FB_2") (pintype "unspecified"))
    )
    (net (code "26") (name "Net-(U1-SW)") (class "Default")
      (node (ref "L2") (pin "1") (pinfunction "1_1") (pintype "unspecified"))
      (node (ref "S1") (pin "2") (pinfunction "2_2") (pintype "unspecified"))
      (node (ref "U1") (pin "3") (pinfunction "SW_3") (pintype "unspecified"))
    )
    (net (code "27") (name "Net-(U1-VC)") (class "Default")
      (node (ref "C12") (pin "1") (pinfunction "1_1") (pintype "unspecified"))
      (node (ref "U1") (pin "4") (pinfunction "VC_4") (pintype "unspecified"))
    )
    (net (code "28") (name "Net-(U1-VIN)") (class "Default")
      (node (ref "C12") (pin "2") (pinfunction "2_2") (pintype "unspecified"))
      (node (ref "C8") (pin "1") (pinfunction "1_1") (pintype "unspecified"))
      (node (ref "CAP3") (pin "1") (pinfunction "1_1") (pintype "unspecified"))
      (node (ref "CAP7") (pin "1") (pinfunction "1_1") (pintype "input"))
      (node (ref "F2") (pin "2") (pinfunction "2_2") (pintype "unspecified"))
      (node (ref "U1") (pin "5") (pinfunction "VIN_5") (pintype "unspecified"))
    )
    (net (code "29") (name "Net-(U2-FB)") (class "Default")
      (node (ref "POTANT2") (pin "2") (pinfunction "2_2") (pintype "input"))
      (node (ref "POTANT2") (pin "3") (pinfunction "3_3") (pintype "input"))
      (node (ref "R9") (pin "1") (pinfunction "1_1") (pintype "unspecified"))
      (node (ref "U2") (pin "2") (pinfunction "FB_2") (pintype "unspecified"))
    )
    (net (code "30") (name "Net-(U2-SW)") (class "Default")
      (node (ref "L3") (pin "1") (pinfunction "1_1") (pintype "unspecified"))
      (node (ref "S2") (pin "2") (pinfunction "2_2") (pintype "unspecified"))
      (node (ref "U2") (pin "3") (pinfunction "SW_3") (pintype "unspecified"))
    )
    (net (code "31") (name "Net-(U2-VC)") (class "Default")
      (node (ref "C13") (pin "1") (pinfunction "1_1") (pintype "unspecified"))
      (node (ref "U2") (pin "4") (pinfunction "VC_4") (pintype "unspecified"))
    )
    (net (code "32") (name "Net-(U2-VIN)") (class "Default")
      (node (ref "C13") (pin "2") (pinfunction "2_2") (pintype "unspecified"))
      (node (ref "C9") (pin "1") (pinfunction "1_1") (pintype "unspecified"))
      (node (ref "CAP4") (pin "1") (pinfunction "1_1") (pintype "unspecified"))
      (node (ref "CAP8") (pin "1") (pinfunction "1_1") (pintype "input"))
      (node (ref "F3") (pin "2") (pinfunction "2_2") (pintype "unspecified"))
      (node (ref "U2") (pin "5") (pinfunction "VIN_5") (pintype "unspecified"))
    )
    (net (code "33") (name "Net-(U3-FB)") (class "Default")
      (node (ref "POTANT3") (pin "2") (pinfunction "2_2") (pintype "input"))
      (node (ref "POTANT3") (pin "3") (pinfunction "3_3") (pintype "input"))
      (node (ref "R10") (pin "1") (pinfunction "1_1") (pintype "unspecified"))
      (node (ref "U3") (pin "2") (pinfunction "FB_2") (pintype "unspecified"))
    )
    (net (code "34") (name "Net-(U3-SW)") (class "Default")
      (node (ref "L4") (pin "1") (pinfunction "1_1") (pintype "unspecified"))
      (node (ref "S3") (pin "2") (pinfunction "2_2") (pintype "unspecified"))
      (node (ref "U3") (pin "3") (pinfunction "SW_3") (pintype "unspecified"))
    )
    (net (code "35") (name "Net-(U3-VC)") (class "Default")
      (node (ref "C14") (pin "1") (pinfunction "1_1") (pintype "unspecified"))
      (node (ref "U3") (pin "4") (pinfunction "VC_4") (pintype "unspecified"))
    )
    (net (code "36") (name "Net-(U3-VIN)") (class "Default")
      (node (ref "C10") (pin "1") (pinfunction "1_1") (pintype "unspecified"))
      (node (ref "C14") (pin "2") (pinfunction "2_2") (pintype "unspecified"))
      (node (ref "CAP5") (pin "1") (pinfunction "1_1") (pintype "unspecified"))
      (node (ref "CAP9") (pin "1") (pinfunction "1_1") (pintype "input"))
      (node (ref "F4") (pin "2") (pinfunction "2_2") (pintype "unspecified"))
      (node (ref "U3") (pin "5") (pinfunction "VIN_5") (pintype "unspecified"))
    )
    (net (code "37") (name "Net-(U4-FB)") (class "Default")
      (node (ref "POTANT4") (pin "2") (pinfunction "2_2") (pintype "input"))
      (node (ref "POTANT4") (pin "3") (pinfunction "3_3") (pintype "input"))
      (node (ref "R11") (pin "1") (pinfunction "1_1") (pintype "unspecified"))
      (node (ref "U4") (pin "2") (pinfunction "FB_2") (pintype "unspecified"))
    )
    (net (code "38") (name "Net-(U4-SW)") (class "Default")
      (node (ref "L5") (pin "1") (pinfunction "1_1") (pintype "unspecified"))
      (node (ref "S4") (pin "2") (pinfunction "2_2") (pintype "unspecified"))
      (node (ref "U4") (pin "3") (pinfunction "SW_3") (pintype "unspecified"))
    )
    (net (code "39") (name "Net-(U4-VC)") (class "Default")
      (node (ref "C15") (pin "2") (pinfunction "2_2") (pintype "unspecified"))
      (node (ref "U4") (pin "4") (pinfunction "VC_4") (pintype "unspecified"))
    )
    (net (code "40") (name "Net-(U4-VIN)") (class "Default")
      (node (ref "C11") (pin "1") (pinfunction "1_1") (pintype "unspecified"))
      (node (ref "C15") (pin "1") (pinfunction "1_1") (pintype "unspecified"))
      (node (ref "CAP10") (pin "1") (pinfunction "1_1") (pintype "input"))
      (node (ref "CAP6") (pin "1") (pinfunction "1_1") (pintype "unspecified"))
      (node (ref "F5") (pin "2") (pinfunction "2_2") (pintype "unspecified"))
      (node (ref "U4") (pin "5") (pinfunction "VIN_5") (pintype "unspecified"))
    )
    (net (code "41") (name "VCC") (class "Default")
      (node (ref "DD1") (pin "2") (pinfunction "A_2") (pintype "unspecified"))
      (node (ref "DR1") (pin "2") (pinfunction "2_2") (pintype "unspecified"))
      (node (ref "DR5") (pin "2") (pinfunction "2_2") (pintype "unspecified"))
    )
    (net (code "42") (name "VIN") (class "Default")
      (node (ref "DC6") (pin "2") (pinfunction "2_2") (pintype "unspecified"))
      (node (ref "DR2") (pin "2") (pinfunction "2_2") (pintype "unspecified"))
      (node (ref "U0") (pin "7") (pinfunction "VIN_7") (pintype "unspecified"))
    )
  )
)
